# Aux_Power_Board_V1.net
KiCad netlist of a schematic drawn in EAGLE
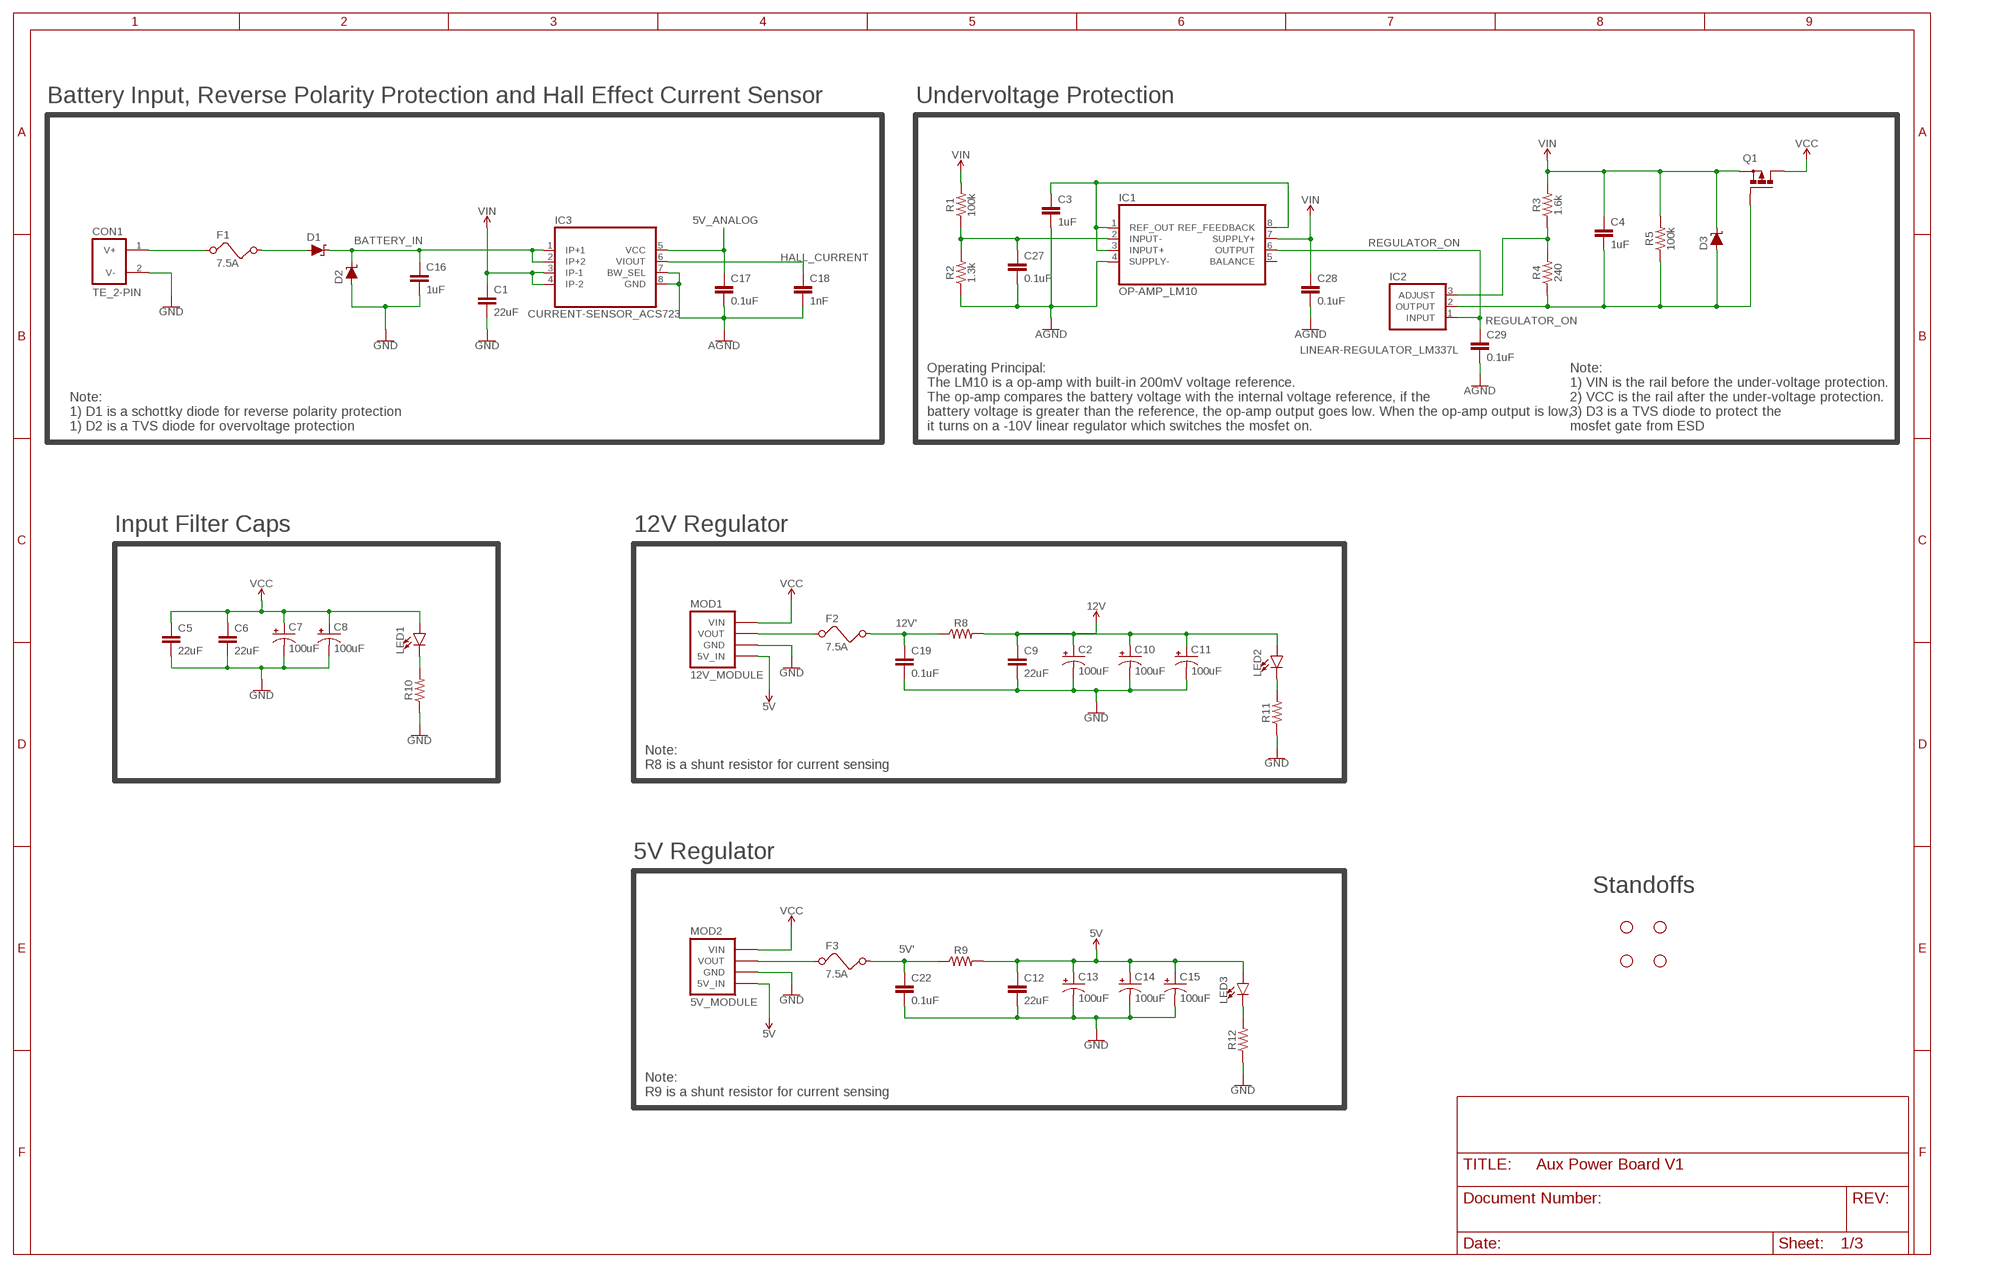
[diagram p0: schematic, sheet 1]
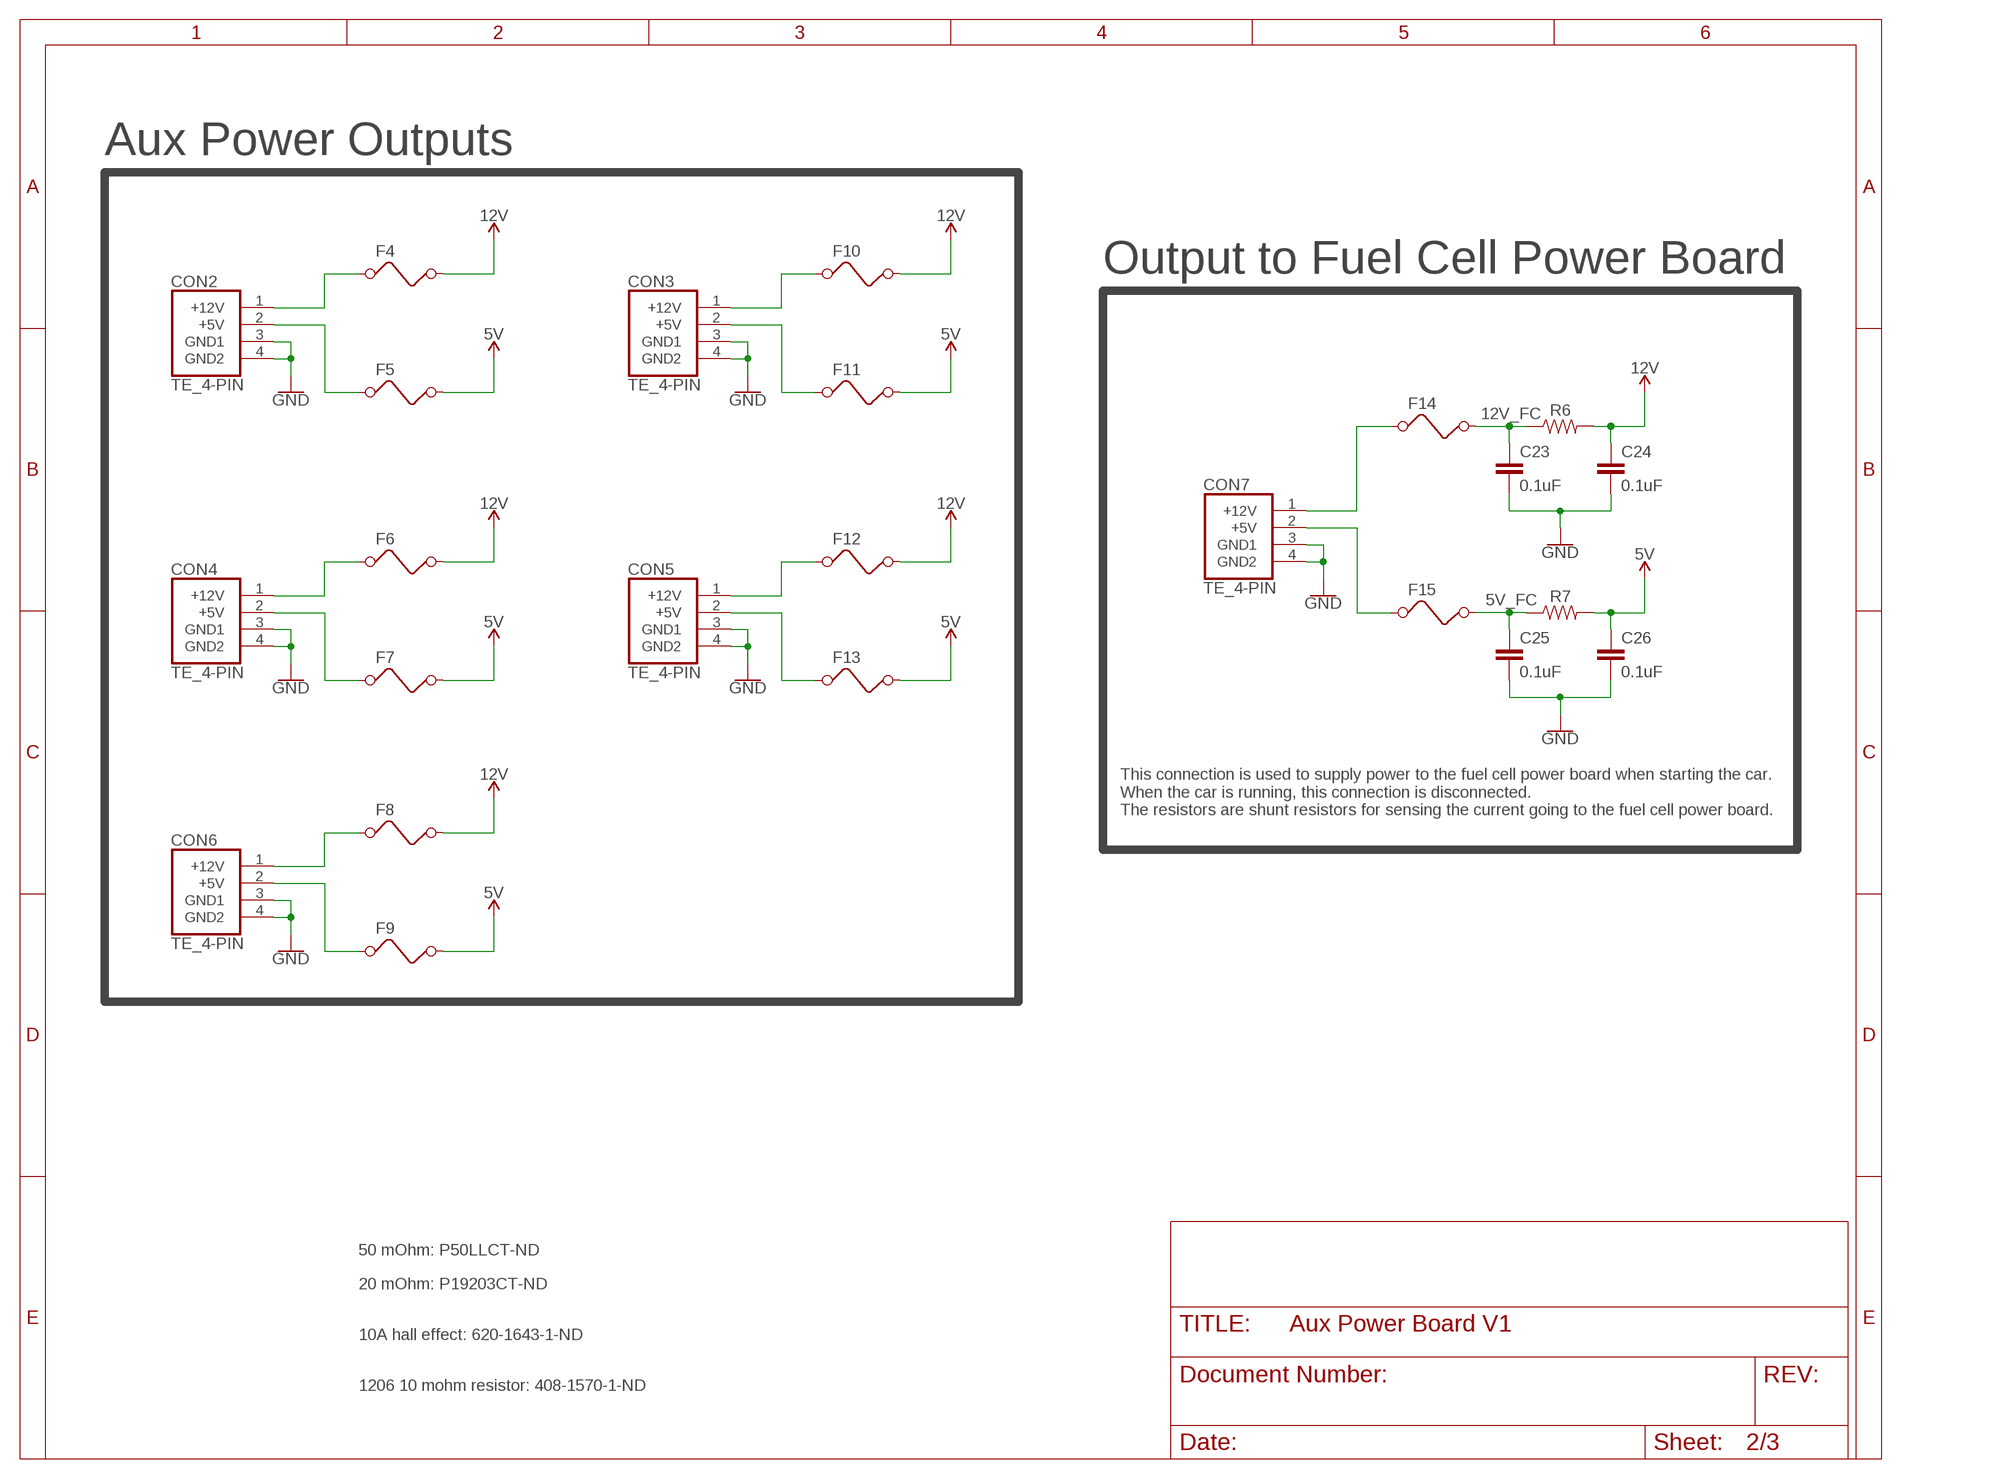
[diagram p1: schematic, sheet 2]
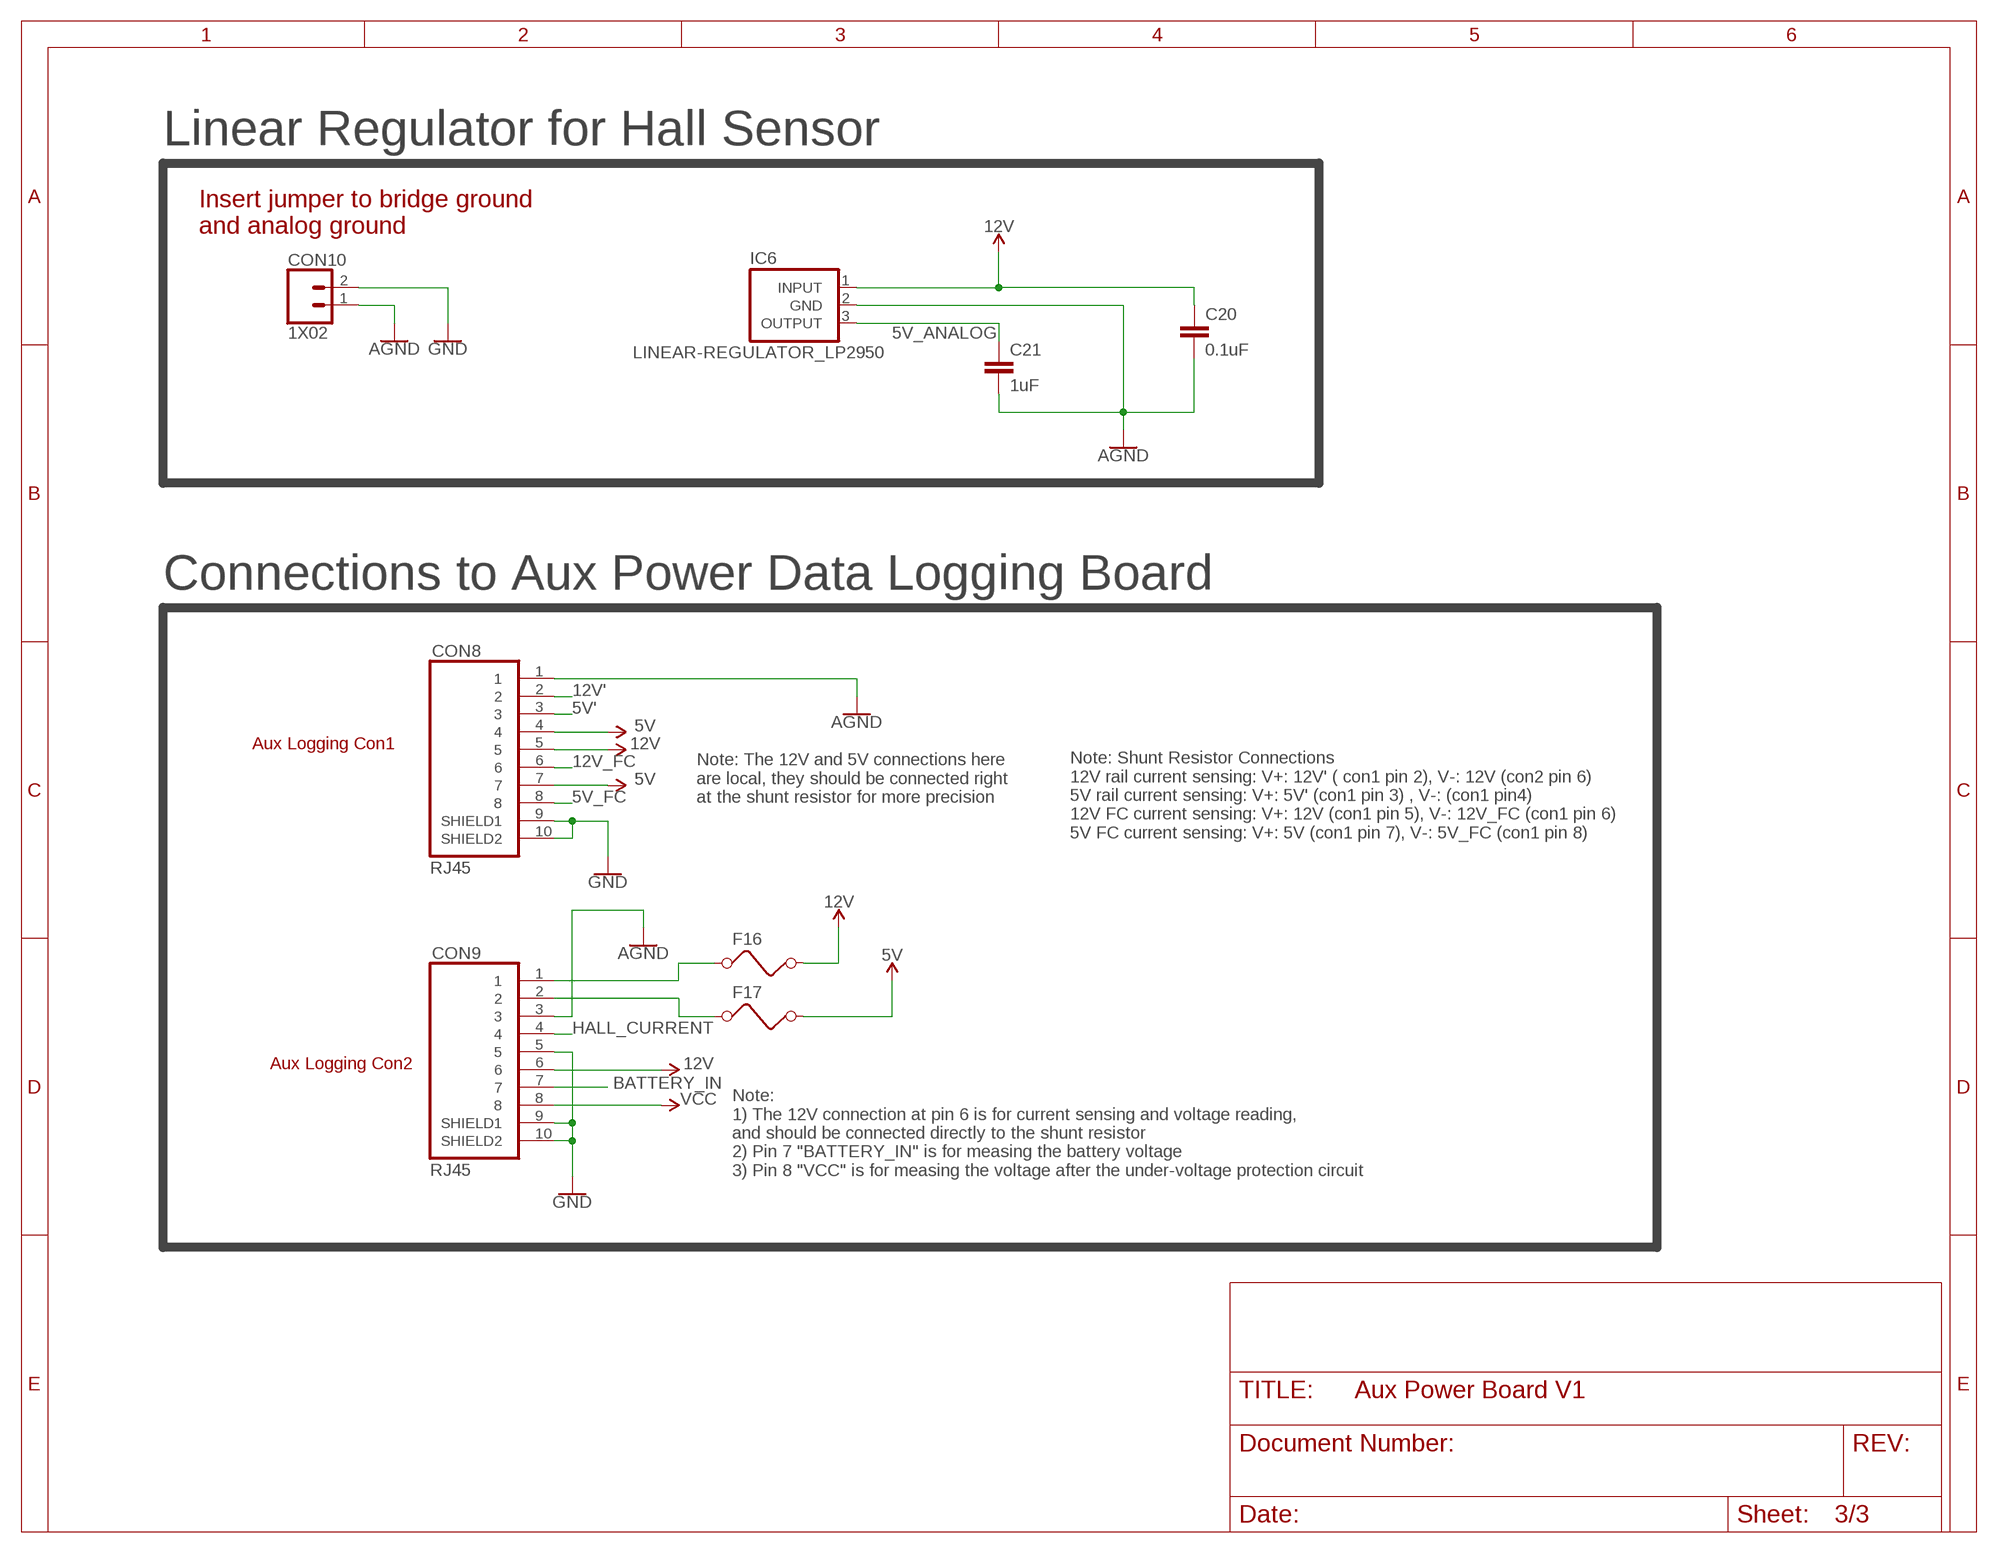
[diagram p2: schematic, sheet 3]

(export (version "E")
  (design (tool "Eeschema 10.0.6"))
  (components
    (comp (ref "C20")
      (value "0.1uF")
      (footprint "eagle-import:0805")
      (libsource (lib "eagle-import") (part "CAPACITOR_0805"))
    )
    (comp (ref "C21")
      (value "1uF")
      (footprint "eagle-import:0805")
      (libsource (lib "eagle-import") (part "CAPACITOR_0805"))
    )
    (comp (ref "CON8")
      (value "RJ45")
      (footprint "eagle-import:RJ45")
      (libsource (lib "eagle-import") (part "RJ45"))
    )
    (comp (ref "CON9")
      (value "RJ45")
      (footprint "eagle-import:RJ45")
      (libsource (lib "eagle-import") (part "RJ45"))
    )
    (comp (ref "CON10")
      (value "1X02")
      (footprint "eagle-import:1X02")
      (libsource (lib "eagle-import") (part "1X02"))
    )
    (comp (ref "F16")
      (value "FUSE_1210")
      (footprint "eagle-import:1210")
      (libsource (lib "eagle-import") (part "FUSE_1210"))
    )
    (comp (ref "F17")
      (value "FUSE_1210")
      (footprint "eagle-import:1210")
      (libsource (lib "eagle-import") (part "FUSE_1210"))
    )
    (comp (ref "IC6")
      (value "LINEAR-REGULATOR_LP2950")
      (footprint "eagle-import:TO92")
      (libsource (lib "eagle-import") (part "LINEAR-REGULATOR_LP2950"))
    )
    (comp (ref "C1")
      (value "22uF")
      (footprint "eagle-import:1210")
      (libsource (lib "eagle-import") (part "CAPACITOR_1210"))
    )
    (comp (ref "C2")
      (value "100uF")
      (footprint "eagle-import:CAPACITOR_100UF_50V")
      (libsource (lib "eagle-import") (part "CAPACITOR_ELECTROLYTIC_100UF"))
    )
    (comp (ref "C3")
      (value "1uF")
      (footprint "eagle-import:0805")
      (libsource (lib "eagle-import") (part "CAPACITOR_0805"))
    )
    (comp (ref "C4")
      (value "1uF")
      (footprint "eagle-import:0805")
      (libsource (lib "eagle-import") (part "CAPACITOR_0805"))
    )
    (comp (ref "C5")
      (value "22uF")
      (footprint "eagle-import:1210")
      (libsource (lib "eagle-import") (part "CAPACITOR_1210"))
    )
    (comp (ref "C6")
      (value "22uF")
      (footprint "eagle-import:1210")
      (libsource (lib "eagle-import") (part "CAPACITOR_1210"))
    )
    (comp (ref "C7")
      (value "100uF")
      (footprint "eagle-import:CAPACITOR_100UF_50V")
      (libsource (lib "eagle-import") (part "CAPACITOR_ELECTROLYTIC_100UF"))
    )
    (comp (ref "C8")
      (value "100uF")
      (footprint "eagle-import:CAPACITOR_100UF_50V")
      (libsource (lib "eagle-import") (part "CAPACITOR_ELECTROLYTIC_100UF"))
    )
    (comp (ref "C9")
      (value "22uF")
      (footprint "eagle-import:0805")
      (libsource (lib "eagle-import") (part "CAPACITOR_0805"))
    )
    (comp (ref "C10")
      (value "100uF")
      (footprint "eagle-import:CAPACITOR_100UF_50V")
      (libsource (lib "eagle-import") (part "CAPACITOR_ELECTROLYTIC_100UF"))
    )
    (comp (ref "C11")
      (value "100uF")
      (footprint "eagle-import:CAPACITOR_100UF_50V")
      (libsource (lib "eagle-import") (part "CAPACITOR_ELECTROLYTIC_100UF"))
    )
    (comp (ref "C12")
      (value "22uF")
      (footprint "eagle-import:0805")
      (libsource (lib "eagle-import") (part "CAPACITOR_0805"))
    )
    (comp (ref "C13")
      (value "100uF")
      (footprint "eagle-import:CAPACITOR_100UF_50V")
      (libsource (lib "eagle-import") (part "CAPACITOR_ELECTROLYTIC_100UF"))
    )
    (comp (ref "C14")
      (value "100uF")
      (footprint "eagle-import:CAPACITOR_100UF_50V")
      (libsource (lib "eagle-import") (part "CAPACITOR_ELECTROLYTIC_100UF"))
    )
    (comp (ref "C15")
      (value "100uF")
      (footprint "eagle-import:CAPACITOR_100UF_50V")
      (libsource (lib "eagle-import") (part "CAPACITOR_ELECTROLYTIC_100UF"))
    )
    (comp (ref "C16")
      (value "1uF")
      (footprint "eagle-import:0805")
      (libsource (lib "eagle-import") (part "CAPACITOR_0805"))
    )
    (comp (ref "C17")
      (value "0.1uF")
      (footprint "eagle-import:0805")
      (libsource (lib "eagle-import") (part "CAPACITOR_0805"))
    )
    (comp (ref "C18")
      (value "1nF")
      (footprint "eagle-import:0805")
      (libsource (lib "eagle-import") (part "CAPACITOR_0805"))
    )
    (comp (ref "C19")
      (value "0.1uF")
      (footprint "eagle-import:0805")
      (libsource (lib "eagle-import") (part "CAPACITOR_0805"))
    )
    (comp (ref "C22")
      (value "0.1uF")
      (footprint "eagle-import:0805")
      (libsource (lib "eagle-import") (part "CAPACITOR_0805"))
    )
    (comp (ref "C27")
      (value "0.1uF")
      (footprint "eagle-import:0805")
      (libsource (lib "eagle-import") (part "CAPACITOR_0805"))
    )
    (comp (ref "C28")
      (value "0.1uF")
      (footprint "eagle-import:0805")
      (libsource (lib "eagle-import") (part "CAPACITOR_0805"))
    )
    (comp (ref "C29")
      (value "0.1uF")
      (footprint "eagle-import:0805")
      (libsource (lib "eagle-import") (part "CAPACITOR_0805"))
    )
    (comp (ref "CON1")
      (value "TE_2-PIN")
      (footprint "eagle-import:TE_2-PIN")
      (libsource (lib "eagle-import") (part "TE_2-PIN"))
    )
    (comp (ref "D1")
      (value "DIODE_SCHOTTKY_TO-263")
      (footprint "eagle-import:TO-263_D2PAK")
      (libsource (lib "eagle-import") (part "DIODE_SCHOTTKY_TO-263"))
    )
    (comp (ref "D2")
      (value "DIODE_TVS_DO-214AA")
      (footprint "eagle-import:DO214AA")
      (libsource (lib "eagle-import") (part "DIODE_TVS_DO-214AA"))
    )
    (comp (ref "D3")
      (value "DIODE_TVS_DO-214AA")
      (footprint "eagle-import:DO214AA")
      (libsource (lib "eagle-import") (part "DIODE_TVS_DO-214AA"))
    )
    (comp (ref "F1")
      (value "7.5A")
      (footprint "eagle-import:FUSEHOLDER_VERTICAL")
      (libsource (lib "eagle-import") (part "FUSEHOLDER_VERTICAL"))
    )
    (comp (ref "F2")
      (value "7.5A")
      (footprint "eagle-import:FUSEHOLDER_VERTICAL")
      (libsource (lib "eagle-import") (part "FUSEHOLDER_VERTICAL"))
    )
    (comp (ref "F3")
      (value "7.5A")
      (footprint "eagle-import:FUSEHOLDER_VERTICAL")
      (libsource (lib "eagle-import") (part "FUSEHOLDER_VERTICAL"))
    )
    (comp (ref "H1")
      (value "STAND-OFF")
      (footprint "eagle-import:STAND-OFF")
      (libsource (lib "eagle-import") (part "STAND-OFF"))
    )
    (comp (ref "H2")
      (value "STAND-OFF")
      (footprint "eagle-import:STAND-OFF")
      (libsource (lib "eagle-import") (part "STAND-OFF"))
    )
    (comp (ref "H3")
      (value "STAND-OFF")
      (footprint "eagle-import:STAND-OFF")
      (libsource (lib "eagle-import") (part "STAND-OFF"))
    )
    (comp (ref "H4")
      (value "STAND-OFF")
      (footprint "eagle-import:STAND-OFF")
      (libsource (lib "eagle-import") (part "STAND-OFF"))
    )
    (comp (ref "IC1")
      (value "OP-AMP_LM10")
      (footprint "eagle-import:DIP08")
      (libsource (lib "eagle-import") (part "OP-AMP_LM10"))
    )
    (comp (ref "IC2")
      (value "LINEAR-REGULATOR_LM337L")
      (footprint "eagle-import:TO92")
      (libsource (lib "eagle-import") (part "LINEAR-REGULATOR_LM337L"))
    )
    (comp (ref "IC3")
      (value "CURRENT-SENSOR_ACS723")
      (footprint "eagle-import:SOIC8")
      (libsource (lib "eagle-import") (part "CURRENT-SENSOR_ACS723"))
    )
    (comp (ref "LED1")
      (value "LED_0805")
      (footprint "eagle-import:0805_LED")
      (libsource (lib "eagle-import") (part "LED_0805"))
    )
    (comp (ref "LED2")
      (value "LED_0805")
      (footprint "eagle-import:0805_LED")
      (libsource (lib "eagle-import") (part "LED_0805"))
    )
    (comp (ref "LED3")
      (value "LED_0805")
      (footprint "eagle-import:0805_LED")
      (libsource (lib "eagle-import") (part "LED_0805"))
    )
    (comp (ref "MOD1")
      (value "12V_MODULE")
      (footprint "eagle-import:5_12V_MODULE")
      (libsource (lib "eagle-import") (part "12V_MODULE"))
    )
    (comp (ref "MOD2")
      (value "5V_MODULE")
      (footprint "eagle-import:5_12V_MODULE")
      (libsource (lib "eagle-import") (part "5V_MODULE"))
    )
    (comp (ref "Q1")
      (value "MOSFET_PMOS_TO-263")
      (footprint "eagle-import:TO-263_D2PAK")
      (libsource (lib "eagle-import") (part "MOSFET_PMOS_TO-263"))
    )
    (comp (ref "R1")
      (value "100k")
      (footprint "eagle-import:0805")
      (libsource (lib "eagle-import") (part "RESISTOR_0805"))
    )
    (comp (ref "R2")
      (value "1.3k")
      (footprint "eagle-import:0805")
      (libsource (lib "eagle-import") (part "RESISTOR_0805"))
    )
    (comp (ref "R3")
      (value "1.6k")
      (footprint "eagle-import:0805")
      (libsource (lib "eagle-import") (part "RESISTOR_0805"))
    )
    (comp (ref "R4")
      (value "240")
      (footprint "eagle-import:0805")
      (libsource (lib "eagle-import") (part "RESISTOR_0805"))
    )
    (comp (ref "R5")
      (value "100k")
      (footprint "eagle-import:0805")
      (libsource (lib "eagle-import") (part "RESISTOR_0805"))
    )
    (comp (ref "R8")
      (value "RESISTOR_1210")
      (footprint "eagle-import:1210")
      (libsource (lib "eagle-import") (part "RESISTOR_1210"))
    )
    (comp (ref "R9")
      (value "RESISTOR_1210")
      (footprint "eagle-import:1210")
      (libsource (lib "eagle-import") (part "RESISTOR_1210"))
    )
    (comp (ref "R10")
      (value "RESISTOR_0805")
      (footprint "eagle-import:0805")
      (libsource (lib "eagle-import") (part "RESISTOR_0805"))
    )
    (comp (ref "R11")
      (value "RESISTOR_0805")
      (footprint "eagle-import:0805")
      (libsource (lib "eagle-import") (part "RESISTOR_0805"))
    )
    (comp (ref "R12")
      (value "RESISTOR_0805")
      (footprint "eagle-import:0805")
      (libsource (lib "eagle-import") (part "RESISTOR_0805"))
    )
    (comp (ref "C23")
      (value "0.1uF")
      (footprint "eagle-import:0805")
      (libsource (lib "eagle-import") (part "CAPACITOR_0805"))
    )
    (comp (ref "C24")
      (value "0.1uF")
      (footprint "eagle-import:0805")
      (libsource (lib "eagle-import") (part "CAPACITOR_0805"))
    )
    (comp (ref "C25")
      (value "0.1uF")
      (footprint "eagle-import:0805")
      (libsource (lib "eagle-import") (part "CAPACITOR_0805"))
    )
    (comp (ref "C26")
      (value "0.1uF")
      (footprint "eagle-import:0805")
      (libsource (lib "eagle-import") (part "CAPACITOR_0805"))
    )
    (comp (ref "CON2")
      (value "TE_4-PIN")
      (footprint "eagle-import:TE_4-PIN")
      (libsource (lib "eagle-import") (part "TE_4-PIN"))
    )
    (comp (ref "CON3")
      (value "TE_4-PIN")
      (footprint "eagle-import:TE_4-PIN")
      (libsource (lib "eagle-import") (part "TE_4-PIN"))
    )
    (comp (ref "CON4")
      (value "TE_4-PIN")
      (footprint "eagle-import:TE_4-PIN")
      (libsource (lib "eagle-import") (part "TE_4-PIN"))
    )
    (comp (ref "CON5")
      (value "TE_4-PIN")
      (footprint "eagle-import:TE_4-PIN")
      (libsource (lib "eagle-import") (part "TE_4-PIN"))
    )
    (comp (ref "CON6")
      (value "TE_4-PIN")
      (footprint "eagle-import:TE_4-PIN")
      (libsource (lib "eagle-import") (part "TE_4-PIN"))
    )
    (comp (ref "CON7")
      (value "TE_4-PIN")
      (footprint "eagle-import:TE_4-PIN")
      (libsource (lib "eagle-import") (part "TE_4-PIN"))
    )
    (comp (ref "F4")
      (value "FUSE_1210")
      (footprint "eagle-import:1210")
      (libsource (lib "eagle-import") (part "FUSE_1210"))
    )
    (comp (ref "F5")
      (value "FUSE_1210")
      (footprint "eagle-import:1210")
      (libsource (lib "eagle-import") (part "FUSE_1210"))
    )
    (comp (ref "F6")
      (value "FUSE_1210")
      (footprint "eagle-import:1210")
      (libsource (lib "eagle-import") (part "FUSE_1210"))
    )
    (comp (ref "F7")
      (value "FUSE_1210")
      (footprint "eagle-import:1210")
      (libsource (lib "eagle-import") (part "FUSE_1210"))
    )
    (comp (ref "F8")
      (value "FUSE_1210")
      (footprint "eagle-import:1210")
      (libsource (lib "eagle-import") (part "FUSE_1210"))
    )
    (comp (ref "F9")
      (value "FUSE_1210")
      (footprint "eagle-import:1210")
      (libsource (lib "eagle-import") (part "FUSE_1210"))
    )
    (comp (ref "F10")
      (value "FUSE_1210")
      (footprint "eagle-import:1210")
      (libsource (lib "eagle-import") (part "FUSE_1210"))
    )
    (comp (ref "F11")
      (value "FUSE_1210")
      (footprint "eagle-import:1210")
      (libsource (lib "eagle-import") (part "FUSE_1210"))
    )
    (comp (ref "F12")
      (value "FUSE_1210")
      (footprint "eagle-import:1210")
      (libsource (lib "eagle-import") (part "FUSE_1210"))
    )
    (comp (ref "F13")
      (value "FUSE_1210")
      (footprint "eagle-import:1210")
      (libsource (lib "eagle-import") (part "FUSE_1210"))
    )
    (comp (ref "F14")
      (value "FUSE_1210")
      (footprint "eagle-import:1210")
      (libsource (lib "eagle-import") (part "FUSE_1210"))
    )
    (comp (ref "F15")
      (value "FUSE_1210")
      (footprint "eagle-import:1210")
      (libsource (lib "eagle-import") (part "FUSE_1210"))
    )
    (comp (ref "R6")
      (value "RESISTOR_1210")
      (footprint "eagle-import:1210")
      (libsource (lib "eagle-import") (part "RESISTOR_1210"))
    )
    (comp (ref "R7")
      (value "RESISTOR_1210")
      (footprint "eagle-import:1210")
      (libsource (lib "eagle-import") (part "RESISTOR_1210"))
    )
  )
  (nets
    (net (code "1") (name "5V") (class "Default")
      (node (ref "C12") (pin "1") (pinfunction "1_1") (pintype "passive"))
      (node (ref "C13") (pin "+") (pinfunction "+_+") (pintype "passive"))
      (node (ref "C14") (pin "+") (pinfunction "+_+") (pintype "passive"))
      (node (ref "C15") (pin "+") (pinfunction "+_+") (pintype "passive"))
      (node (ref "C26") (pin "1") (pinfunction "1_1") (pintype "passive"))
      (node (ref "CON8") (pin "4") (pinfunction "4_4") (pintype "passive"))
      (node (ref "CON8") (pin "7") (pinfunction "7_7") (pintype "passive"))
      (node (ref "F11") (pin "2") (pinfunction "2_2") (pintype "passive"))
      (node (ref "F13") (pin "2") (pinfunction "2_2") (pintype "passive"))
      (node (ref "F17") (pin "2") (pinfunction "2_2") (pintype "passive"))
      (node (ref "F5") (pin "2") (pinfunction "2_2") (pintype "passive"))
      (node (ref "F7") (pin "2") (pinfunction "2_2") (pintype "passive"))
      (node (ref "F9") (pin "2") (pinfunction "2_2") (pintype "passive"))
      (node (ref "LED3") (pin "1") (pinfunction "A_1") (pintype "passive"))
      (node (ref "MOD1") (pin "P$32") (pinfunction "5V_IN_P$32") (pintype "bidirectional"))
      (node (ref "MOD2") (pin "P$32") (pinfunction "5V_IN_P$32") (pintype "bidirectional"))
      (node (ref "R7") (pin "2") (pinfunction "2_2") (pintype "passive"))
      (node (ref "R9") (pin "2") (pinfunction "2_2") (pintype "passive"))
    )
    (net (code "2") (name "5V'") (class "Default")
      (node (ref "C22") (pin "1") (pinfunction "1_1") (pintype "passive"))
      (node (ref "CON8") (pin "3") (pinfunction "3_3") (pintype "passive"))
      (node (ref "F3") (pin "3") (pinfunction "2_3") (pintype "passive"))
      (node (ref "F3") (pin "4") (pinfunction "2_4") (pintype "passive"))
      (node (ref "R9") (pin "1") (pinfunction "1_1") (pintype "passive"))
    )
    (net (code "3") (name "5V_ANALOG") (class "Default")
      (node (ref "C17") (pin "1") (pinfunction "1_1") (pintype "passive"))
      (node (ref "C21") (pin "1") (pinfunction "1_1") (pintype "passive"))
      (node (ref "IC3") (pin "5") (pinfunction "VCC_5") (pintype "bidirectional"))
      (node (ref "IC6") (pin "3") (pinfunction "OUTPUT_3") (pintype "bidirectional"))
    )
    (net (code "4") (name "5V_FC") (class "Default")
      (node (ref "C25") (pin "1") (pinfunction "1_1") (pintype "passive"))
      (node (ref "CON8") (pin "8") (pinfunction "8_8") (pintype "passive"))
      (node (ref "F15") (pin "2") (pinfunction "2_2") (pintype "passive"))
      (node (ref "R7") (pin "1") (pinfunction "1_1") (pintype "passive"))
    )
    (net (code "5") (name "12V") (class "Default")
      (node (ref "C10") (pin "+") (pinfunction "+_+") (pintype "passive"))
      (node (ref "C11") (pin "+") (pinfunction "+_+") (pintype "passive"))
      (node (ref "C2") (pin "+") (pinfunction "+_+") (pintype "passive"))
      (node (ref "C20") (pin "1") (pinfunction "1_1") (pintype "passive"))
      (node (ref "C24") (pin "1") (pinfunction "1_1") (pintype "passive"))
      (node (ref "C9") (pin "1") (pinfunction "1_1") (pintype "passive"))
      (node (ref "CON8") (pin "5") (pinfunction "5_5") (pintype "passive"))
      (node (ref "CON9") (pin "6") (pinfunction "6_6") (pintype "passive"))
      (node (ref "F10") (pin "2") (pinfunction "2_2") (pintype "passive"))
      (node (ref "F12") (pin "2") (pinfunction "2_2") (pintype "passive"))
      (node (ref "F16") (pin "2") (pinfunction "2_2") (pintype "passive"))
      (node (ref "F4") (pin "2") (pinfunction "2_2") (pintype "passive"))
      (node (ref "F6") (pin "2") (pinfunction "2_2") (pintype "passive"))
      (node (ref "F8") (pin "2") (pinfunction "2_2") (pintype "passive"))
      (node (ref "IC6") (pin "1") (pinfunction "INPUT_1") (pintype "bidirectional"))
      (node (ref "LED2") (pin "1") (pinfunction "A_1") (pintype "passive"))
      (node (ref "R6") (pin "2") (pinfunction "2_2") (pintype "passive"))
      (node (ref "R8") (pin "2") (pinfunction "2_2") (pintype "passive"))
    )
    (net (code "6") (name "12V'") (class "Default")
      (node (ref "C19") (pin "1") (pinfunction "1_1") (pintype "passive"))
      (node (ref "CON8") (pin "2") (pinfunction "2_2") (pintype "passive"))
      (node (ref "F2") (pin "3") (pinfunction "2_3") (pintype "passive"))
      (node (ref "F2") (pin "4") (pinfunction "2_4") (pintype "passive"))
      (node (ref "R8") (pin "1") (pinfunction "1_1") (pintype "passive"))
    )
    (net (code "7") (name "12V_FC") (class "Default")
      (node (ref "C23") (pin "1") (pinfunction "1_1") (pintype "passive"))
      (node (ref "CON8") (pin "6") (pinfunction "6_6") (pintype "passive"))
      (node (ref "F14") (pin "2") (pinfunction "2_2") (pintype "passive"))
      (node (ref "R6") (pin "1") (pinfunction "1_1") (pintype "passive"))
    )
    (net (code "8") (name "AGND") (class "Default")
      (node (ref "C17") (pin "2") (pinfunction "2_2") (pintype "passive"))
      (node (ref "C18") (pin "2") (pinfunction "2_2") (pintype "passive"))
      (node (ref "C20") (pin "2") (pinfunction "2_2") (pintype "passive"))
      (node (ref "C21") (pin "2") (pinfunction "2_2") (pintype "passive"))
      (node (ref "C27") (pin "2") (pinfunction "2_2") (pintype "passive"))
      (node (ref "C28") (pin "2") (pinfunction "2_2") (pintype "passive"))
      (node (ref "C29") (pin "2") (pinfunction "2_2") (pintype "passive"))
      (node (ref "C3") (pin "2") (pinfunction "2_2") (pintype "passive"))
      (node (ref "CON10") (pin "1") (pinfunction "1_1") (pintype "passive"))
      (node (ref "CON8") (pin "1") (pinfunction "1_1") (pintype "passive"))
      (node (ref "CON9") (pin "3") (pinfunction "3_3") (pintype "passive"))
      (node (ref "IC1") (pin "4") (pinfunction "SUPPLY-_4") (pintype "bidirectional"))
      (node (ref "IC3") (pin "7") (pinfunction "BW_SEL_7") (pintype "bidirectional"))
      (node (ref "IC3") (pin "8") (pinfunction "GND_8") (pintype "bidirectional"))
      (node (ref "IC6") (pin "2") (pinfunction "GND_2") (pintype "bidirectional"))
      (node (ref "R2") (pin "1") (pinfunction "1_1") (pintype "passive"))
    )
    (net (code "9") (name "BATTERY_IN") (class "Default")
      (node (ref "C16") (pin "1") (pinfunction "1_1") (pintype "passive"))
      (node (ref "CON9") (pin "7") (pinfunction "7_7") (pintype "passive"))
      (node (ref "D1") (pin "2") (pinfunction "C_2") (pintype "passive"))
      (node (ref "D2") (pin "C") (pinfunction "C_C") (pintype "passive"))
      (node (ref "IC3") (pin "1") (pinfunction "IP+1_1") (pintype "bidirectional"))
      (node (ref "IC3") (pin "2") (pinfunction "IP+2_2") (pintype "bidirectional"))
    )
    (net (code "10") (name "GND") (class "Default")
      (node (ref "C1") (pin "2") (pinfunction "2_2") (pintype "passive"))
      (node (ref "C10") (pin "-") (pinfunction "-_-") (pintype "passive"))
      (node (ref "C11") (pin "-") (pinfunction "-_-") (pintype "passive"))
      (node (ref "C12") (pin "2") (pinfunction "2_2") (pintype "passive"))
      (node (ref "C13") (pin "-") (pinfunction "-_-") (pintype "passive"))
      (node (ref "C14") (pin "-") (pinfunction "-_-") (pintype "passive"))
      (node (ref "C15") (pin "-") (pinfunction "-_-") (pintype "passive"))
      (node (ref "C16") (pin "2") (pinfunction "2_2") (pintype "passive"))
      (node (ref "C19") (pin "2") (pinfunction "2_2") (pintype "passive"))
      (node (ref "C2") (pin "-") (pinfunction "-_-") (pintype "passive"))
      (node (ref "C22") (pin "2") (pinfunction "2_2") (pintype "passive"))
      (node (ref "C23") (pin "2") (pinfunction "2_2") (pintype "passive"))
      (node (ref "C24") (pin "2") (pinfunction "2_2") (pintype "passive"))
      (node (ref "C25") (pin "2") (pinfunction "2_2") (pintype "passive"))
      (node (ref "C26") (pin "2") (pinfunction "2_2") (pintype "passive"))
      (node (ref "C5") (pin "2") (pinfunction "2_2") (pintype "passive"))
      (node (ref "C6") (pin "2") (pinfunction "2_2") (pintype "passive"))
      (node (ref "C7") (pin "-") (pinfunction "-_-") (pintype "passive"))
      (node (ref "C8") (pin "-") (pinfunction "-_-") (pintype "passive"))
      (node (ref "C9") (pin "2") (pinfunction "2_2") (pintype "passive"))
      (node (ref "CON1") (pin "2") (pinfunction "V-_2") (pintype "passive"))
      (node (ref "CON10") (pin "2") (pinfunction "2_2") (pintype "passive"))
      (node (ref "CON2") (pin "3") (pinfunction "GND1_3") (pintype "passive"))
      (node (ref "CON2") (pin "4") (pinfunction "GND2_4") (pintype "passive"))
      (node (ref "CON3") (pin "3") (pinfunction "GND1_3") (pintype "passive"))
      (node (ref "CON3") (pin "4") (pinfunction "GND2_4") (pintype "passive"))
      (node (ref "CON4") (pin "3") (pinfunction "GND1_3") (pintype "passive"))
      (node (ref "CON4") (pin "4") (pinfunction "GND2_4") (pintype "passive"))
      (node (ref "CON5") (pin "3") (pinfunction "GND1_3") (pintype "passive"))
      (node (ref "CON5") (pin "4") (pinfunction "GND2_4") (pintype "passive"))
      (node (ref "CON6") (pin "3") (pinfunction "GND1_3") (pintype "passive"))
      (node (ref "CON6") (pin "4") (pinfunction "GND2_4") (pintype "passive"))
      (node (ref "CON7") (pin "3") (pinfunction "GND1_3") (pintype "passive"))
      (node (ref "CON7") (pin "4") (pinfunction "GND2_4") (pintype "passive"))
      (node (ref "CON8") (pin "10") (pinfunction "SHIELD2_10") (pintype "passive"))
      (node (ref "CON8") (pin "9") (pinfunction "SHIELD1_9") (pintype "passive"))
      (node (ref "CON9") (pin "10") (pinfunction "SHIELD2_10") (pintype "passive"))
      (node (ref "CON9") (pin "5") (pinfunction "5_5") (pintype "passive"))
      (node (ref "CON9") (pin "9") (pinfunction "SHIELD1_9") (pintype "passive"))
      (node (ref "D2") (pin "A") (pinfunction "A_A") (pintype "passive"))
      (node (ref "MOD1") (pin "P$25") (pinfunction "GND_P$25") (pintype "passive"))
      (node (ref "MOD1") (pin "P$26") (pinfunction "GND_P$26") (pintype "passive"))
      (node (ref "MOD1") (pin "P$27") (pinfunction "GND_P$27") (pintype "passive"))
      (node (ref "MOD1") (pin "P$28") (pinfunction "GND_P$28") (pintype "passive"))
      (node (ref "MOD1") (pin "P$29") (pinfunction "GND_P$29") (pintype "passive"))
      (node (ref "MOD1") (pin "P$30") (pinfunction "GND_P$30") (pintype "passive"))
      (node (ref "MOD1") (pin "P$31") (pinfunction "GND_P$31") (pintype "passive"))
      (node (ref "MOD2") (pin "P$25") (pinfunction "GND_P$25") (pintype "passive"))
      (node (ref "MOD2") (pin "P$26") (pinfunction "GND_P$26") (pintype "passive"))
      (node (ref "MOD2") (pin "P$27") (pinfunction "GND_P$27") (pintype "passive"))
      (node (ref "MOD2") (pin "P$28") (pinfunction "GND_P$28") (pintype "passive"))
      (node (ref "MOD2") (pin "P$29") (pinfunction "GND_P$29") (pintype "passive"))
      (node (ref "MOD2") (pin "P$30") (pinfunction "GND_P$30") (pintype "passive"))
      (node (ref "MOD2") (pin "P$31") (pinfunction "GND_P$31") (pintype "passive"))
      (node (ref "R10") (pin "1") (pinfunction "1_1") (pintype "passive"))
      (node (ref "R11") (pin "1") (pinfunction "1_1") (pintype "passive"))
      (node (ref "R12") (pin "1") (pinfunction "1_1") (pintype "passive"))
    )
    (net (code "11") (name "HALL_CURRENT") (class "Default")
      (node (ref "C18") (pin "1") (pinfunction "1_1") (pintype "passive"))
      (node (ref "CON9") (pin "4") (pinfunction "4_4") (pintype "passive"))
      (node (ref "IC3") (pin "6") (pinfunction "VIOUT_6") (pintype "bidirectional"))
    )
    (net (code "12") (name "Net-(CON1-V+)") (class "Default")
      (node (ref "CON1") (pin "1") (pinfunction "V+_1") (pintype "passive"))
      (node (ref "F1") (pin "1") (pinfunction "1_1") (pintype "passive"))
      (node (ref "F1") (pin "2") (pinfunction "1_2") (pintype "passive"))
    )
    (net (code "13") (name "Net-(CON2-+5V)") (class "Default")
      (node (ref "CON2") (pin "2") (pinfunction "+5V_2") (pintype "passive"))
      (node (ref "F5") (pin "1") (pinfunction "1_1") (pintype "passive"))
    )
    (net (code "14") (name "Net-(CON2-+12V)") (class "Default")
      (node (ref "CON2") (pin "1") (pinfunction "+12V_1") (pintype "passive"))
      (node (ref "F4") (pin "1") (pinfunction "1_1") (pintype "passive"))
    )
    (net (code "15") (name "Net-(CON3-+5V)") (class "Default")
      (node (ref "CON3") (pin "2") (pinfunction "+5V_2") (pintype "passive"))
      (node (ref "F11") (pin "1") (pinfunction "1_1") (pintype "passive"))
    )
    (net (code "16") (name "Net-(CON3-+12V)") (class "Default")
      (node (ref "CON3") (pin "1") (pinfunction "+12V_1") (pintype "passive"))
      (node (ref "F10") (pin "1") (pinfunction "1_1") (pintype "passive"))
    )
    (net (code "17") (name "Net-(CON4-+5V)") (class "Default")
      (node (ref "CON4") (pin "2") (pinfunction "+5V_2") (pintype "passive"))
      (node (ref "F7") (pin "1") (pinfunction "1_1") (pintype "passive"))
    )
    (net (code "18") (name "Net-(CON4-+12V)") (class "Default")
      (node (ref "CON4") (pin "1") (pinfunction "+12V_1") (pintype "passive"))
      (node (ref "F6") (pin "1") (pinfunction "1_1") (pintype "passive"))
    )
    (net (code "19") (name "Net-(CON5-+5V)") (class "Default")
      (node (ref "CON5") (pin "2") (pinfunction "+5V_2") (pintype "passive"))
      (node (ref "F13") (pin "1") (pinfunction "1_1") (pintype "passive"))
    )
    (net (code "20") (name "Net-(CON5-+12V)") (class "Default")
      (node (ref "CON5") (pin "1") (pinfunction "+12V_1") (pintype "passive"))
      (node (ref "F12") (pin "1") (pinfunction "1_1") (pintype "passive"))
    )
    (net (code "21") (name "Net-(CON6-+5V)") (class "Default")
      (node (ref "CON6") (pin "2") (pinfunction "+5V_2") (pintype "passive"))
      (node (ref "F9") (pin "1") (pinfunction "1_1") (pintype "passive"))
    )
    (net (code "22") (name "Net-(CON6-+12V)") (class "Default")
      (node (ref "CON6") (pin "1") (pinfunction "+12V_1") (pintype "passive"))
      (node (ref "F8") (pin "1") (pinfunction "1_1") (pintype "passive"))
    )
    (net (code "23") (name "Net-(CON7-+5V)") (class "Default")
      (node (ref "CON7") (pin "2") (pinfunction "+5V_2") (pintype "passive"))
      (node (ref "F15") (pin "1") (pinfunction "1_1") (pintype "passive"))
    )
    (net (code "24") (name "Net-(CON7-+12V)") (class "Default")
      (node (ref "CON7") (pin "1") (pinfunction "+12V_1") (pintype "passive"))
      (node (ref "F14") (pin "1") (pinfunction "1_1") (pintype "passive"))
    )
    (net (code "25") (name "Net-(CON9-Pad1)") (class "Default")
      (node (ref "CON9") (pin "1") (pinfunction "1_1") (pintype "passive"))
      (node (ref "F16") (pin "1") (pinfunction "1_1") (pintype "passive"))
    )
    (net (code "26") (name "Net-(CON9-Pad2)") (class "Default")
      (node (ref "CON9") (pin "2") (pinfunction "2_2") (pintype "passive"))
      (node (ref "F17") (pin "1") (pinfunction "1_1") (pintype "passive"))
    )
    (net (code "27") (name "Net-(D1-A)") (class "Default")
      (node (ref "D1") (pin "3") (pinfunction "A_3") (pintype "passive"))
      (node (ref "F1") (pin "3") (pinfunction "2_3") (pintype "passive"))
      (node (ref "F1") (pin "4") (pinfunction "2_4") (pintype "passive"))
    )
    (net (code "28") (name "Net-(F2-1-Pad2)") (class "Default")
      (node (ref "F2") (pin "1") (pinfunction "1_1") (pintype "passive"))
      (node (ref "F2") (pin "2") (pinfunction "1_2") (pintype "passive"))
      (node (ref "MOD1") (pin "P$10") (pinfunction "VOUT_P$10") (pintype "passive"))
      (node (ref "MOD1") (pin "P$11") (pinfunction "VOUT_P$11") (pintype "passive"))
      (node (ref "MOD1") (pin "P$12") (pinfunction "VOUT_P$12") (pintype "passive"))
      (node (ref "MOD1") (pin "P$13") (pinfunction "VOUT_P$13") (pintype "passive"))
      (node (ref "MOD1") (pin "P$14") (pinfunction "VOUT_P$14") (pintype "passive"))
      (node (ref "MOD1") (pin "P$15") (pinfunction "VOUT_P$15") (pintype "passive"))
      (node (ref "MOD1") (pin "P$16") (pinfunction "VOUT_P$16") (pintype "passive"))
      (node (ref "MOD1") (pin "P$17") (pinfunction "VOUT_P$17") (pintype "passive"))
      (node (ref "MOD1") (pin "P$18") (pinfunction "VOUT_P$18") (pintype "passive"))
      (node (ref "MOD1") (pin "P$19") (pinfunction "VOUT_P$19") (pintype "passive"))
      (node (ref "MOD1") (pin "P$20") (pinfunction "VOUT_P$20") (pintype "passive"))
      (node (ref "MOD1") (pin "P$21") (pinfunction "VOUT_P$21") (pintype "passive"))
      (node (ref "MOD1") (pin "P$22") (pinfunction "VOUT_P$22") (pintype "passive"))
      (node (ref "MOD1") (pin "P$23") (pinfunction "VOUT_P$23") (pintype "passive"))
      (node (ref "MOD1") (pin "P$24") (pinfunction "VOUT_P$24") (pintype "passive"))
      (node (ref "MOD1") (pin "P$9") (pinfunction "VOUT_P$9") (pintype "passive"))
    )
    (net (code "29") (name "Net-(F3-1-Pad2)") (class "Default")
      (node (ref "F3") (pin "1") (pinfunction "1_1") (pintype "passive"))
      (node (ref "F3") (pin "2") (pinfunction "1_2") (pintype "passive"))
      (node (ref "MOD2") (pin "P$10") (pinfunction "VOUT_P$10") (pintype "passive"))
      (node (ref "MOD2") (pin "P$11") (pinfunction "VOUT_P$11") (pintype "passive"))
      (node (ref "MOD2") (pin "P$12") (pinfunction "VOUT_P$12") (pintype "passive"))
      (node (ref "MOD2") (pin "P$13") (pinfunction "VOUT_P$13") (pintype "passive"))
      (node (ref "MOD2") (pin "P$14") (pinfunction "VOUT_P$14") (pintype "passive"))
      (node (ref "MOD2") (pin "P$15") (pinfunction "VOUT_P$15") (pintype "passive"))
      (node (ref "MOD2") (pin "P$16") (pinfunction "VOUT_P$16") (pintype "passive"))
      (node (ref "MOD2") (pin "P$17") (pinfunction "VOUT_P$17") (pintype "passive"))
      (node (ref "MOD2") (pin "P$18") (pinfunction "VOUT_P$18") (pintype "passive"))
      (node (ref "MOD2") (pin "P$19") (pinfunction "VOUT_P$19") (pintype "passive"))
      (node (ref "MOD2") (pin "P$20") (pinfunction "VOUT_P$20") (pintype "passive"))
      (node (ref "MOD2") (pin "P$21") (pinfunction "VOUT_P$21") (pintype "passive"))
      (node (ref "MOD2") (pin "P$22") (pinfunction "VOUT_P$22") (pintype "passive"))
      (node (ref "MOD2") (pin "P$23") (pinfunction "VOUT_P$23") (pintype "passive"))
      (node (ref "MOD2") (pin "P$24") (pinfunction "VOUT_P$24") (pintype "passive"))
      (node (ref "MOD2") (pin "P$9") (pinfunction "VOUT_P$9") (pintype "passive"))
    )
    (net (code "30") (name "Net-(IC1-INPUT+)") (class "Default")
      (node (ref "C3") (pin "1") (pinfunction "1_1") (pintype "passive"))
      (node (ref "IC1") (pin "1") (pinfunction "REF_OUT_1") (pintype "bidirectional"))
      (node (ref "IC1") (pin "3") (pinfunction "INPUT+_3") (pintype "bidirectional"))
      (node (ref "IC1") (pin "8") (pinfunction "REF_FEEDBACK_8") (pintype "bidirectional"))
    )
    (net (code "31") (name "Net-(IC1-INPUT-)") (class "Default")
      (node (ref "C27") (pin "1") (pinfunction "1_1") (pintype "passive"))
      (node (ref "IC1") (pin "2") (pinfunction "INPUT-_2") (pintype "bidirectional"))
      (node (ref "R1") (pin "1") (pinfunction "1_1") (pintype "passive"))
      (node (ref "R2") (pin "2") (pinfunction "2_2") (pintype "passive"))
    )
    (net (code "32") (name "Net-(IC2-ADJUST)") (class "Default")
      (node (ref "IC2") (pin "3") (pinfunction "ADJUST_3") (pintype "bidirectional"))
      (node (ref "R3") (pin "1") (pinfunction "1_1") (pintype "passive"))
      (node (ref "R4") (pin "2") (pinfunction "2_2") (pintype "passive"))
    )
    (net (code "33") (name "Net-(IC2-OUTPUT)") (class "Default")
      (node (ref "C4") (pin "2") (pinfunction "2_2") (pintype "passive"))
      (node (ref "D3") (pin "A") (pinfunction "A_A") (pintype "passive"))
      (node (ref "IC2") (pin "2") (pinfunction "OUTPUT_2") (pintype "bidirectional"))
      (node (ref "Q1") (pin "1") (pinfunction "G_1") (pintype "passive"))
      (node (ref "R4") (pin "1") (pinfunction "1_1") (pintype "passive"))
      (node (ref "R5") (pin "1") (pinfunction "1_1") (pintype "passive"))
    )
    (net (code "34") (name "Net-(LED1-C)") (class "Default")
      (node (ref "LED1") (pin "2") (pinfunction "C_2") (pintype "passive"))
      (node (ref "R10") (pin "2") (pinfunction "2_2") (pintype "passive"))
    )
    (net (code "35") (name "Net-(LED2-C)") (class "Default")
      (node (ref "LED2") (pin "2") (pinfunction "C_2") (pintype "passive"))
      (node (ref "R11") (pin "2") (pinfunction "2_2") (pintype "passive"))
    )
    (net (code "36") (name "Net-(LED3-C)") (class "Default")
      (node (ref "LED3") (pin "2") (pinfunction "C_2") (pintype "passive"))
      (node (ref "R12") (pin "2") (pinfunction "2_2") (pintype "passive"))
    )
    (net (code "37") (name "REGULATOR_ON") (class "Default")
      (node (ref "C29") (pin "1") (pinfunction "1_1") (pintype "passive"))
      (node (ref "IC1") (pin "6") (pinfunction "OUTPUT_6") (pintype "bidirectional"))
      (node (ref "IC2") (pin "1") (pinfunction "INPUT_1") (pintype "bidirectional"))
    )
    (net (code "38") (name "VCC") (class "Default")
      (node (ref "C5") (pin "1") (pinfunction "1_1") (pintype "passive"))
      (node (ref "C6") (pin "1") (pinfunction "1_1") (pintype "passive"))
      (node (ref "C7") (pin "+") (pinfunction "+_+") (pintype "passive"))
      (node (ref "C8") (pin "+") (pinfunction "+_+") (pintype "passive"))
      (node (ref "CON9") (pin "8") (pinfunction "8_8") (pintype "passive"))
      (node (ref "LED1") (pin "1") (pinfunction "A_1") (pintype "passive"))
      (node (ref "MOD1") (pin "P$1") (pinfunction "VIN_P$1") (pintype "passive"))
      (node (ref "MOD1") (pin "P$2") (pinfunction "VIN_P$2") (pintype "passive"))
      (node (ref "MOD1") (pin "P$3") (pinfunction "VIN_P$3") (pintype "passive"))
      (node (ref "MOD1") (pin "P$4") (pinfunction "VIN_P$4") (pintype "passive"))
      (node (ref "MOD1") (pin "P$5") (pinfunction "VIN_P$5") (pintype "passive"))
      (node (ref "MOD1") (pin "P$6") (pinfunction "VIN_P$6") (pintype "passive"))
      (node (ref "MOD1") (pin "P$7") (pinfunction "VIN_P$7") (pintype "passive"))
      (node (ref "MOD1") (pin "P$8") (pinfunction "VIN_P$8") (pintype "passive"))
      (node (ref "MOD2") (pin "P$1") (pinfunction "VIN_P$1") (pintype "passive"))
      (node (ref "MOD2") (pin "P$2") (pinfunction "VIN_P$2") (pintype "passive"))
      (node (ref "MOD2") (pin "P$3") (pinfunction "VIN_P$3") (pintype "passive"))
      (node (ref "MOD2") (pin "P$4") (pinfunction "VIN_P$4") (pintype "passive"))
      (node (ref "MOD2") (pin "P$5") (pinfunction "VIN_P$5") (pintype "passive"))
      (node (ref "MOD2") (pin "P$6") (pinfunction "VIN_P$6") (pintype "passive"))
      (node (ref "MOD2") (pin "P$7") (pinfunction "VIN_P$7") (pintype "passive"))
      (node (ref "MOD2") (pin "P$8") (pinfunction "VIN_P$8") (pintype "passive"))
      (node (ref "Q1") (pin "2") (pinfunction "D_2") (pintype "passive"))
    )
    (net (code "39") (name "VIN") (class "Default")
      (node (ref "C1") (pin "1") (pinfunction "1_1") (pintype "passive"))
      (node (ref "C28") (pin "1") (pinfunction "1_1") (pintype "passive"))
      (node (ref "C4") (pin "1") (pinfunction "1_1") (pintype "passive"))
      (node (ref "D3") (pin "C") (pinfunction "C_C") (pintype "passive"))
      (node (ref "IC1") (pin "7") (pinfunction "SUPPLY+_7") (pintype "bidirectional"))
      (node (ref "IC3") (pin "3") (pinfunction "IP-1_3") (pintype "bidirectional"))
      (node (ref "IC3") (pin "4") (pinfunction "IP-2_4") (pintype "bidirectional"))
      (node (ref "Q1") (pin "3") (pinfunction "S_3") (pintype "passive"))
      (node (ref "R1") (pin "2") (pinfunction "2_2") (pintype "passive"))
      (node (ref "R3") (pin "2") (pinfunction "2_2") (pintype "passive"))
      (node (ref "R5") (pin "2") (pinfunction "2_2") (pintype "passive"))
    )
    (net (code "40") (name "unconnected-(IC1-BALANCE-Pad5)") (class "Default")
      (node (ref "IC1") (pin "5") (pinfunction "BALANCE_5") (pintype "bidirectional"))
    )
  )
)
